# PWR.net
KiCad netlist of a schematic drawn in Altium Designer
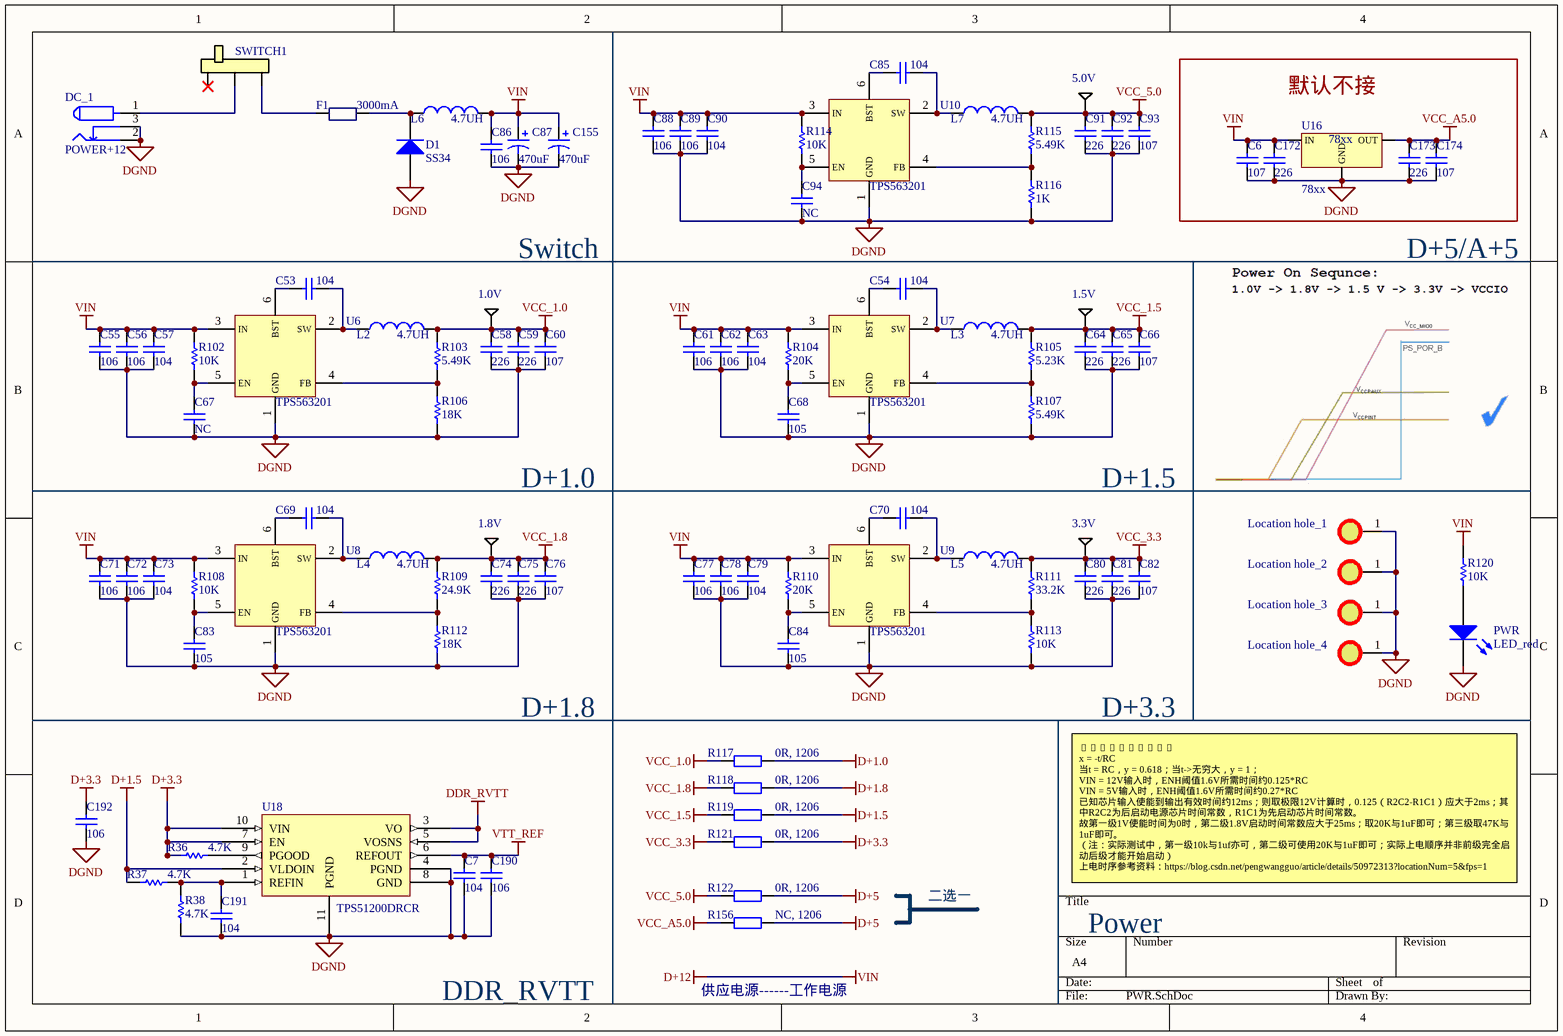
[diagram p0: PWR.SchDoc]

(export (version "E")
  (design (tool "Eeschema 10.0.6"))
  (components
    (comp (ref "1.0V")
      (value "Test")
      (footprint "Test Point")
      (description "Test Point")
      (libsource (lib "ZYNQ7010_add") (part "Test"))
    )
    (comp (ref "1.5V")
      (value "Test")
      (footprint "Test Point")
      (description "Test Point")
      (libsource (lib "ZYNQ7010_add") (part "Test"))
    )
    (comp (ref "1.8V")
      (value "Test")
      (footprint "Test Point")
      (description "Test Point")
      (libsource (lib "ZYNQ7010_add") (part "Test"))
    )
    (comp (ref "3.3V")
      (value "Test")
      (footprint "Test Point")
      (description "Test Point")
      (libsource (lib "ZYNQ7010_add") (part "Test"))
    )
    (comp (ref "5.0V")
      (value "Test")
      (footprint "Test Point")
      (description "Test Point")
      (libsource (lib "ZYNQ7010_add") (part "Test"))
    )
    (comp (ref "C6")
      (value "107")
      (footprint "C 1206_L")
      (description "Capacitor")
      (fields (field (name "PUBLISHER") "Altium Limited"))
      (libsource (lib "Miscellaneous Devices") (part "Cap"))
    )
    (comp (ref "C7")
      (value "104")
      (footprint "C 0402_LL")
      (description "Capacitor")
      (fields (field (name "PUBLISHER") "Altium Limited"))
      (libsource (lib "Miscellaneous Devices") (part "Cap"))
    )
    (comp (ref "C53")
      (value "104")
      (footprint "C 0402_LL")
      (description "Capacitor")
      (fields (field (name "PUBLISHER") "Altium Limited"))
      (libsource (lib "Miscellaneous Devices") (part "Cap"))
    )
    (comp (ref "C54")
      (value "104")
      (footprint "C 0402_LL")
      (description "Capacitor")
      (fields (field (name "PUBLISHER") "Altium Limited"))
      (libsource (lib "Miscellaneous Devices") (part "Cap"))
    )
    (comp (ref "C55")
      (value "106")
      (footprint "C 0805_L")
      (description "Capacitor")
      (fields (field (name "PUBLISHER") "Altium Limited"))
      (libsource (lib "Miscellaneous Devices") (part "Cap"))
    )
    (comp (ref "C56")
      (value "106")
      (footprint "C 0805_L")
      (description "Capacitor")
      (fields (field (name "PUBLISHER") "Altium Limited"))
      (libsource (lib "Miscellaneous Devices") (part "Cap"))
    )
    (comp (ref "C57")
      (value "104")
      (footprint "C 0402_LL")
      (description "Capacitor")
      (fields (field (name "PUBLISHER") "Altium Limited"))
      (libsource (lib "Miscellaneous Devices") (part "Cap"))
    )
    (comp (ref "C58")
      (value "226")
      (footprint "C 0805_L")
      (description "Capacitor")
      (fields (field (name "PUBLISHER") "Altium Limited"))
      (libsource (lib "Miscellaneous Devices") (part "Cap"))
    )
    (comp (ref "C59")
      (value "226")
      (footprint "C 0805_L")
      (description "Capacitor")
      (fields (field (name "PUBLISHER") "Altium Limited"))
      (libsource (lib "Miscellaneous Devices") (part "Cap"))
    )
    (comp (ref "C60")
      (value "107")
      (footprint "C 1206_L")
      (description "Capacitor")
      (fields (field (name "PUBLISHER") "Altium Limited"))
      (libsource (lib "Miscellaneous Devices") (part "Cap"))
    )
    (comp (ref "C61")
      (value "106")
      (footprint "C 0805_L")
      (description "Capacitor")
      (fields (field (name "PUBLISHER") "Altium Limited"))
      (libsource (lib "Miscellaneous Devices") (part "Cap"))
    )
    (comp (ref "C62")
      (value "106")
      (footprint "C 0805_L")
      (description "Capacitor")
      (fields (field (name "PUBLISHER") "Altium Limited"))
      (libsource (lib "Miscellaneous Devices") (part "Cap"))
    )
    (comp (ref "C63")
      (value "104")
      (footprint "C 0402_LL")
      (description "Capacitor")
      (fields (field (name "PUBLISHER") "Altium Limited"))
      (libsource (lib "Miscellaneous Devices") (part "Cap"))
    )
    (comp (ref "C64")
      (value "226")
      (footprint "C 0805_L")
      (description "Capacitor")
      (fields (field (name "PUBLISHER") "Altium Limited"))
      (libsource (lib "Miscellaneous Devices") (part "Cap"))
    )
    (comp (ref "C65")
      (value "226")
      (footprint "C 0805_L")
      (description "Capacitor")
      (fields (field (name "PUBLISHER") "Altium Limited"))
      (libsource (lib "Miscellaneous Devices") (part "Cap"))
    )
    (comp (ref "C66")
      (value "107")
      (footprint "C 1206_L")
      (description "Capacitor")
      (fields (field (name "PUBLISHER") "Altium Limited"))
      (libsource (lib "Miscellaneous Devices") (part "Cap"))
    )
    (comp (ref "C67")
      (value "NC")
      (footprint "C 0402_LL")
      (description "Capacitor")
      (fields (field (name "PUBLISHER") "Altium Limited"))
      (libsource (lib "Miscellaneous Devices") (part "Cap"))
    )
    (comp (ref "C68")
      (value "105")
      (footprint "C 0402_LL")
      (description "Capacitor")
      (fields (field (name "PUBLISHER") "Altium Limited"))
      (libsource (lib "Miscellaneous Devices") (part "Cap"))
    )
    (comp (ref "C69")
      (value "104")
      (footprint "C 0402_LL")
      (description "Capacitor")
      (fields (field (name "PUBLISHER") "Altium Limited"))
      (libsource (lib "Miscellaneous Devices") (part "Cap"))
    )
    (comp (ref "C70")
      (value "104")
      (footprint "C 0402_LL")
      (description "Capacitor")
      (fields (field (name "PUBLISHER") "Altium Limited"))
      (libsource (lib "Miscellaneous Devices") (part "Cap"))
    )
    (comp (ref "C71")
      (value "106")
      (footprint "C 0805_L")
      (description "Capacitor")
      (fields (field (name "PUBLISHER") "Altium Limited"))
      (libsource (lib "Miscellaneous Devices") (part "Cap"))
    )
    (comp (ref "C72")
      (value "106")
      (footprint "C 0805_L")
      (description "Capacitor")
      (fields (field (name "PUBLISHER") "Altium Limited"))
      (libsource (lib "Miscellaneous Devices") (part "Cap"))
    )
    (comp (ref "C73")
      (value "104")
      (footprint "C 0402_LL")
      (description "Capacitor")
      (fields (field (name "PUBLISHER") "Altium Limited"))
      (libsource (lib "Miscellaneous Devices") (part "Cap"))
    )
    (comp (ref "C74")
      (value "226")
      (footprint "C 0805_L")
      (description "Capacitor")
      (fields (field (name "PUBLISHER") "Altium Limited"))
      (libsource (lib "Miscellaneous Devices") (part "Cap"))
    )
    (comp (ref "C75")
      (value "226")
      (footprint "C 0805_L")
      (description "Capacitor")
      (fields (field (name "PUBLISHER") "Altium Limited"))
      (libsource (lib "Miscellaneous Devices") (part "Cap"))
    )
    (comp (ref "C76")
      (value "107")
      (footprint "C 1206_L")
      (description "Capacitor")
      (fields (field (name "PUBLISHER") "Altium Limited"))
      (libsource (lib "Miscellaneous Devices") (part "Cap"))
    )
    (comp (ref "C77")
      (value "106")
      (footprint "C 0805_L")
      (description "Capacitor")
      (fields (field (name "PUBLISHER") "Altium Limited"))
      (libsource (lib "Miscellaneous Devices") (part "Cap"))
    )
    (comp (ref "C78")
      (value "106")
      (footprint "C 0805_L")
      (description "Capacitor")
      (fields (field (name "PUBLISHER") "Altium Limited"))
      (libsource (lib "Miscellaneous Devices") (part "Cap"))
    )
    (comp (ref "C79")
      (value "104")
      (footprint "C 0402_LL")
      (description "Capacitor")
      (fields (field (name "PUBLISHER") "Altium Limited"))
      (libsource (lib "Miscellaneous Devices") (part "Cap"))
    )
    (comp (ref "C80")
      (value "226")
      (footprint "C 0805_L")
      (description "Capacitor")
      (fields (field (name "PUBLISHER") "Altium Limited"))
      (libsource (lib "Miscellaneous Devices") (part "Cap"))
    )
    (comp (ref "C81")
      (value "226")
      (footprint "C 0805_L")
      (description "Capacitor")
      (fields (field (name "PUBLISHER") "Altium Limited"))
      (libsource (lib "Miscellaneous Devices") (part "Cap"))
    )
    (comp (ref "C82")
      (value "107")
      (footprint "C 1206_L")
      (description "Capacitor")
      (fields (field (name "PUBLISHER") "Altium Limited"))
      (libsource (lib "Miscellaneous Devices") (part "Cap"))
    )
    (comp (ref "C83")
      (value "105")
      (footprint "C 0402_LL")
      (description "Capacitor")
      (fields (field (name "PUBLISHER") "Altium Limited"))
      (libsource (lib "Miscellaneous Devices") (part "Cap"))
    )
    (comp (ref "C84")
      (value "105")
      (footprint "C 0402_LL")
      (description "Capacitor")
      (fields (field (name "PUBLISHER") "Altium Limited"))
      (libsource (lib "Miscellaneous Devices") (part "Cap"))
    )
    (comp (ref "C85")
      (value "104")
      (footprint "C 0402_LL")
      (description "Capacitor")
      (fields (field (name "PUBLISHER") "Altium Limited"))
      (libsource (lib "Miscellaneous Devices") (part "Cap"))
    )
    (comp (ref "C86")
      (value "106")
      (footprint "C 0805_L")
      (description "Capacitor")
      (fields (field (name "PUBLISHER") "Altium Limited"))
      (libsource (lib "Miscellaneous Devices") (part "Cap"))
    )
    (comp (ref "C87")
      (value "470uF")
      (footprint "CD D(7343)")
      (description "Polarized Capacitor (Radial)")
      (fields (field (name "Comment") "Cap Pol1") (field (name "PUBLISHER") "Altium Limited"))
      (libsource (lib "Miscellaneous Devices") (part "Cap Pol1"))
    )
    (comp (ref "C88")
      (value "106")
      (footprint "C 0805_L")
      (description "Capacitor")
      (fields (field (name "PUBLISHER") "Altium Limited"))
      (libsource (lib "Miscellaneous Devices") (part "Cap"))
    )
    (comp (ref "C89")
      (value "106")
      (footprint "C 0805_L")
      (description "Capacitor")
      (fields (field (name "PUBLISHER") "Altium Limited"))
      (libsource (lib "Miscellaneous Devices") (part "Cap"))
    )
    (comp (ref "C90")
      (value "104")
      (footprint "C 0402_LL")
      (description "Capacitor")
      (fields (field (name "PUBLISHER") "Altium Limited"))
      (libsource (lib "Miscellaneous Devices") (part "Cap"))
    )
    (comp (ref "C91")
      (value "226")
      (footprint "C 0805_L")
      (description "Capacitor")
      (fields (field (name "PUBLISHER") "Altium Limited"))
      (libsource (lib "Miscellaneous Devices") (part "Cap"))
    )
    (comp (ref "C92")
      (value "226")
      (footprint "C 0805_L")
      (description "Capacitor")
      (fields (field (name "PUBLISHER") "Altium Limited"))
      (libsource (lib "Miscellaneous Devices") (part "Cap"))
    )
    (comp (ref "C93")
      (value "107")
      (footprint "C 1206_L")
      (description "Capacitor")
      (fields (field (name "PUBLISHER") "Altium Limited"))
      (libsource (lib "Miscellaneous Devices") (part "Cap"))
    )
    (comp (ref "C94")
      (value "NC")
      (footprint "C 0402_LL")
      (description "Capacitor")
      (fields (field (name "PUBLISHER") "Altium Limited"))
      (libsource (lib "Miscellaneous Devices") (part "Cap"))
    )
    (comp (ref "C155")
      (value "470uF")
      (footprint "CD D(7343)")
      (description "Polarized Capacitor (Radial)")
      (fields (field (name "Comment") "Cap Pol1") (field (name "PUBLISHER") "Altium Limited"))
      (libsource (lib "Miscellaneous Devices") (part "Cap Pol1"))
    )
    (comp (ref "C172")
      (value "226")
      (footprint "C 0805_L")
      (description "Capacitor")
      (fields (field (name "PUBLISHER") "Altium Limited"))
      (libsource (lib "Miscellaneous Devices") (part "Cap"))
    )
    (comp (ref "C173")
      (value "226")
      (footprint "C 0805_L")
      (description "Capacitor")
      (fields (field (name "PUBLISHER") "Altium Limited"))
      (libsource (lib "Miscellaneous Devices") (part "Cap"))
    )
    (comp (ref "C174")
      (value "107")
      (footprint "C 1206_L")
      (description "Capacitor")
      (fields (field (name "PUBLISHER") "Altium Limited"))
      (libsource (lib "Miscellaneous Devices") (part "Cap"))
    )
    (comp (ref "C190")
      (value "106")
      (footprint "C 0603_L")
      (description "Capacitor")
      (fields (field (name "PUBLISHER") "Altium Limited"))
      (libsource (lib "Miscellaneous Devices") (part "Cap"))
    )
    (comp (ref "C191")
      (value "104")
      (footprint "C 0402_LL")
      (description "Capacitor")
      (fields (field (name "PUBLISHER") "Altium Limited"))
      (libsource (lib "Miscellaneous Devices") (part "Cap"))
    )
    (comp (ref "C192")
      (value "106")
      (footprint "C 0603_L")
      (description "Capacitor")
      (fields (field (name "PUBLISHER") "Altium Limited"))
      (libsource (lib "Miscellaneous Devices") (part "Cap"))
    )
    (comp (ref "D1")
      (value "SS34")
      (footprint "SMA")
      (description "Default Diode")
      (fields (field (name "PUBLISHER") "Altium Limited"))
      (libsource (lib "Miscellaneous Devices") (part "Diode"))
    )
    (comp (ref "DC_1") (value "POWER+12") (footprint "DC-005") (libsource (lib "Sean") (part "POWER")))
    (comp (ref "F1") (value "3000mA") (footprint "FU 1812") (libsource (lib "Sean") (part "PTC")))
    (comp (ref "L2")
      (value "4.7UH")
      (footprint "NR6045")
      (description "Inductor")
      (fields (field (name "PUBLISHER") "Altium Limited"))
      (libsource (lib "Miscellaneous Devices") (part "Inductor"))
    )
    (comp (ref "L3")
      (value "4.7UH")
      (footprint "NR6045")
      (description "Inductor")
      (fields (field (name "PUBLISHER") "Altium Limited"))
      (libsource (lib "Miscellaneous Devices") (part "Inductor"))
    )
    (comp (ref "L4")
      (value "4.7UH")
      (footprint "NR6045")
      (description "Inductor")
      (fields (field (name "PUBLISHER") "Altium Limited"))
      (libsource (lib "Miscellaneous Devices") (part "Inductor"))
    )
    (comp (ref "L5")
      (value "4.7UH")
      (footprint "NR6045")
      (description "Inductor")
      (fields (field (name "PUBLISHER") "Altium Limited"))
      (libsource (lib "Miscellaneous Devices") (part "Inductor"))
    )
    (comp (ref "L6")
      (value "4.7UH")
      (footprint "NR6045")
      (description "Inductor")
      (fields (field (name "PUBLISHER") "Altium Limited"))
      (libsource (lib "Miscellaneous Devices") (part "Inductor"))
    )
    (comp (ref "L7")
      (value "4.7UH")
      (footprint "NR6045")
      (description "Inductor")
      (fields (field (name "PUBLISHER") "Altium Limited"))
      (libsource (lib "Miscellaneous Devices") (part "Inductor"))
    )
    (comp (ref "Location hole_1")
      (value "Touch")
      (footprint "M3x4+6_N")
      (libsource (lib "Sean") (part "Touch"))
    )
    (comp (ref "Location hole_2")
      (value "Touch")
      (footprint "M3x4+6_N")
      (libsource (lib "Sean") (part "Touch"))
    )
    (comp (ref "Location hole_3")
      (value "Touch")
      (footprint "M3x4+6_N")
      (libsource (lib "Sean") (part "Touch"))
    )
    (comp (ref "Location hole_4")
      (value "Touch")
      (footprint "M3x4+6_N")
      (libsource (lib "Sean") (part "Touch"))
    )
    (comp (ref "PWR")
      (value "LED_red")
      (footprint "LED 0603W")
      (description "Typical INFRARED GaAs LED")
      (fields (field (name "PUBLISHER") "Altium Limited"))
      (libsource (lib "Miscellaneous Devices") (part "LED0"))
    )
    (comp (ref "R36")
      (value "4.7K")
      (footprint "R 0402_L")
      (description "Resistor")
      (fields (field (name "PUBLISHER") "Altium Limited"))
      (libsource (lib "Miscellaneous Devices") (part "Res1"))
    )
    (comp (ref "R37")
      (value "4.7K")
      (footprint "R 0402_L")
      (description "Resistor")
      (fields (field (name "PUBLISHER") "Altium Limited"))
      (libsource (lib "Miscellaneous Devices") (part "Res1"))
    )
    (comp (ref "R38")
      (value "4.7K")
      (footprint "R 0402_L")
      (description "Resistor")
      (fields (field (name "PUBLISHER") "Altium Limited"))
      (libsource (lib "Miscellaneous Devices") (part "Res1"))
    )
    (comp (ref "R102")
      (value "10K")
      (footprint "R 0603_L")
      (description "Resistor")
      (fields (field (name "PUBLISHER") "Altium Limited"))
      (libsource (lib "Miscellaneous Devices") (part "Res1"))
    )
    (comp (ref "R103")
      (value "5.49K")
      (footprint "R 0603_L")
      (description "Resistor")
      (fields (field (name "PUBLISHER") "Altium Limited"))
      (libsource (lib "Miscellaneous Devices") (part "Res1"))
    )
    (comp (ref "R104")
      (value "20K")
      (footprint "R 0603_L")
      (description "Resistor")
      (fields (field (name "PUBLISHER") "Altium Limited"))
      (libsource (lib "Miscellaneous Devices") (part "Res1"))
    )
    (comp (ref "R105")
      (value "5.23K")
      (footprint "R 0603_L")
      (description "Resistor")
      (fields (field (name "PUBLISHER") "Altium Limited"))
      (libsource (lib "Miscellaneous Devices") (part "Res1"))
    )
    (comp (ref "R106")
      (value "18K")
      (footprint "R 0603_L")
      (description "Resistor")
      (fields (field (name "PUBLISHER") "Altium Limited"))
      (libsource (lib "Miscellaneous Devices") (part "Res1"))
    )
    (comp (ref "R107")
      (value "5.49K")
      (footprint "R 0603_L")
      (description "Resistor")
      (fields (field (name "PUBLISHER") "Altium Limited"))
      (libsource (lib "Miscellaneous Devices") (part "Res1"))
    )
    (comp (ref "R108")
      (value "10K")
      (footprint "R 0603_L")
      (description "Resistor")
      (fields (field (name "PUBLISHER") "Altium Limited"))
      (libsource (lib "Miscellaneous Devices") (part "Res1"))
    )
    (comp (ref "R109")
      (value "24.9K")
      (footprint "R 0603_L")
      (description "Resistor")
      (fields (field (name "PUBLISHER") "Altium Limited"))
      (libsource (lib "Miscellaneous Devices") (part "Res1"))
    )
    (comp (ref "R110")
      (value "20K")
      (footprint "R 0603_L")
      (description "Resistor")
      (fields (field (name "PUBLISHER") "Altium Limited"))
      (libsource (lib "Miscellaneous Devices") (part "Res1"))
    )
    (comp (ref "R111")
      (value "33.2K")
      (footprint "R 0603_L")
      (description "Resistor")
      (fields (field (name "PUBLISHER") "Altium Limited"))
      (libsource (lib "Miscellaneous Devices") (part "Res1"))
    )
    (comp (ref "R112")
      (value "18K")
      (footprint "R 0603_L")
      (description "Resistor")
      (fields (field (name "PUBLISHER") "Altium Limited"))
      (libsource (lib "Miscellaneous Devices") (part "Res1"))
    )
    (comp (ref "R113")
      (value "10K")
      (footprint "R 0603_L")
      (description "Resistor")
      (fields (field (name "PUBLISHER") "Altium Limited"))
      (libsource (lib "Miscellaneous Devices") (part "Res1"))
    )
    (comp (ref "R114")
      (value "10K")
      (footprint "R 0603_L")
      (description "Resistor")
      (fields (field (name "PUBLISHER") "Altium Limited"))
      (libsource (lib "Miscellaneous Devices") (part "Res1"))
    )
    (comp (ref "R115")
      (value "5.49K")
      (footprint "R 0603_L")
      (description "Resistor")
      (fields (field (name "PUBLISHER") "Altium Limited"))
      (libsource (lib "Miscellaneous Devices") (part "Res1"))
    )
    (comp (ref "R116")
      (value "1K")
      (footprint "R 0603_L")
      (description "Resistor")
      (fields (field (name "PUBLISHER") "Altium Limited"))
      (libsource (lib "Miscellaneous Devices") (part "Res1"))
    )
    (comp (ref "R117")
      (value "0R, 1206")
      (footprint "R 1206_L")
      (description "Resistor")
      (fields (field (name "PUBLISHER") "Altium Limited"))
      (libsource (lib "Miscellaneous Devices") (part "Res2"))
    )
    (comp (ref "R118")
      (value "0R, 1206")
      (footprint "R 1206_L")
      (description "Resistor")
      (fields (field (name "PUBLISHER") "Altium Limited"))
      (libsource (lib "Miscellaneous Devices") (part "Res2"))
    )
    (comp (ref "R119")
      (value "0R, 1206")
      (footprint "R 1206_L")
      (description "Resistor")
      (fields (field (name "PUBLISHER") "Altium Limited"))
      (libsource (lib "Miscellaneous Devices") (part "Res2"))
    )
    (comp (ref "R120")
      (value "10K")
      (footprint "R 0603_L")
      (description "Resistor")
      (fields (field (name "PUBLISHER") "Altium Limited"))
      (libsource (lib "Miscellaneous Devices") (part "Res1"))
    )
    (comp (ref "R121")
      (value "0R, 1206")
      (footprint "R 1206_L")
      (description "Resistor")
      (fields (field (name "PUBLISHER") "Altium Limited"))
      (libsource (lib "Miscellaneous Devices") (part "Res2"))
    )
    (comp (ref "R122")
      (value "0R, 1206")
      (footprint "R 1206_L")
      (description "Resistor")
      (fields (field (name "PUBLISHER") "Altium Limited"))
      (libsource (lib "Miscellaneous Devices") (part "Res2"))
    )
    (comp (ref "R156")
      (value "NC, 1206")
      (footprint "R 1206_L")
      (description "Resistor")
      (fields (field (name "PUBLISHER") "Altium Limited"))
      (libsource (lib "Miscellaneous Devices") (part "Res2"))
    )
    (comp (ref "SWITCH1")
      (value "Switch")
      (footprint "SS-12D10")
      (libsource (lib "XCZU15_add") (part "Switch"))
    )
    (comp (ref "U6")
      (value "TPS563201")
      (footprint "SOT23-6N")
      (description "TPS563201, BUCK, 3A")
      (libsource (lib "ZYNQ7010_add") (part "TPS563201"))
    )
    (comp (ref "U7")
      (value "TPS563201")
      (footprint "SOT23-6N")
      (description "TPS563201, BUCK, 3A")
      (libsource (lib "ZYNQ7010_add") (part "TPS563201"))
    )
    (comp (ref "U8")
      (value "TPS563201")
      (footprint "SOT23-6N")
      (description "TPS563201, BUCK, 3A")
      (libsource (lib "ZYNQ7010_add") (part "TPS563201"))
    )
    (comp (ref "U9")
      (value "TPS563201")
      (footprint "SOT23-6N")
      (description "TPS563201, BUCK, 3A")
      (libsource (lib "ZYNQ7010_add") (part "TPS563201"))
    )
    (comp (ref "U10")
      (value "TPS563201")
      (footprint "SOT23-6N")
      (description "TPS563201, BUCK, 3A")
      (libsource (lib "ZYNQ7010_add") (part "TPS563201"))
    )
    (comp (ref "U16") (value "78xx") (footprint "TO252") (libsource (lib "Schlib1") (part "78xx")))
    (comp (ref "U18")
      (value "TPS51200DRCR")
      (footprint "VSON")
      (description "DDR 终端稳压器")
      (fields (field (name "MANUFACTURER") "TI"))
      (libsource (lib "ZYNQ7010_add") (part "TPS51200"))
    )
  )
  (nets
    (net (code "1") (name "D+1.0") (class "Default")
      (node (ref "R117") (pin "2") (pinfunction "2_2") (pintype "passive"))
    )
    (net (code "2") (name "D+1.5") (class "Default")
      (node (ref "R119") (pin "2") (pinfunction "2_2") (pintype "passive"))
      (node (ref "R37") (pin "1") (pinfunction "1_1") (pintype "passive"))
      (node (ref "U18") (pin "2") (pinfunction "VLDOIN_2") (pintype "input"))
    )
    (net (code "3") (name "D+1.8") (class "Default")
      (node (ref "R118") (pin "2") (pinfunction "2_2") (pintype "passive"))
    )
    (net (code "4") (name "D+3.3") (class "Default")
      (node (ref "C192") (pin "2") (pinfunction "2_2") (pintype "passive"))
      (node (ref "R121") (pin "2") (pinfunction "2_2") (pintype "passive"))
      (node (ref "R36") (pin "1") (pinfunction "1_1") (pintype "passive"))
      (node (ref "U18") (pin "10") (pinfunction "VIN_10") (pintype "input"))
      (node (ref "U18") (pin "7") (pinfunction "EN_7") (pintype "input"))
    )
    (net (code "5") (name "D+5") (class "Default")
      (node (ref "R122") (pin "2") (pinfunction "2_2") (pintype "passive"))
      (node (ref "R156") (pin "2") (pinfunction "2_2") (pintype "passive"))
    )
    (net (code "6") (name "D+12") (class "Default")
      (node (ref "C155") (pin "1") (pinfunction "1_1") (pintype "passive"))
      (node (ref "C172") (pin "1") (pinfunction "1_1") (pintype "passive"))
      (node (ref "C55") (pin "1") (pinfunction "1_1") (pintype "passive"))
      (node (ref "C56") (pin "1") (pinfunction "1_1") (pintype "passive"))
      (node (ref "C57") (pin "1") (pinfunction "1_1") (pintype "passive"))
      (node (ref "C6") (pin "1") (pinfunction "1_1") (pintype "passive"))
      (node (ref "C61") (pin "1") (pinfunction "1_1") (pintype "passive"))
      (node (ref "C62") (pin "1") (pinfunction "1_1") (pintype "passive"))
      (node (ref "C63") (pin "1") (pinfunction "1_1") (pintype "passive"))
      (node (ref "C71") (pin "1") (pinfunction "1_1") (pintype "passive"))
      (node (ref "C72") (pin "1") (pinfunction "1_1") (pintype "passive"))
      (node (ref "C73") (pin "1") (pinfunction "1_1") (pintype "passive"))
      (node (ref "C77") (pin "1") (pinfunction "1_1") (pintype "passive"))
      (node (ref "C78") (pin "1") (pinfunction "1_1") (pintype "passive"))
      (node (ref "C79") (pin "1") (pinfunction "1_1") (pintype "passive"))
      (node (ref "C86") (pin "1") (pinfunction "1_1") (pintype "passive"))
      (node (ref "C87") (pin "1") (pinfunction "1_1") (pintype "passive"))
      (node (ref "C88") (pin "1") (pinfunction "1_1") (pintype "passive"))
      (node (ref "C89") (pin "1") (pinfunction "1_1") (pintype "passive"))
      (node (ref "C90") (pin "1") (pinfunction "1_1") (pintype "passive"))
      (node (ref "L6") (pin "2") (pinfunction "2_2") (pintype "passive"))
      (node (ref "R102") (pin "2") (pinfunction "2_2") (pintype "passive"))
      (node (ref "R104") (pin "2") (pinfunction "2_2") (pintype "passive"))
      (node (ref "R108") (pin "2") (pinfunction "2_2") (pintype "passive"))
      (node (ref "R110") (pin "2") (pinfunction "2_2") (pintype "passive"))
      (node (ref "R114") (pin "1") (pinfunction "1_1") (pintype "passive"))
      (node (ref "R120") (pin "2") (pinfunction "2_2") (pintype "passive"))
      (node (ref "U10") (pin "3") (pinfunction "IN_3") (pintype "passive"))
      (node (ref "U16") (pin "1") (pinfunction "IN_1") (pintype "passive"))
      (node (ref "U6") (pin "3") (pinfunction "IN_3") (pintype "passive"))
      (node (ref "U7") (pin "3") (pinfunction "IN_3") (pintype "passive"))
      (node (ref "U8") (pin "3") (pinfunction "IN_3") (pintype "passive"))
      (node (ref "U9") (pin "3") (pinfunction "IN_3") (pintype "passive"))
    )
    (net (code "7") (name "DDR_RVTT") (class "Default")
      (node (ref "U18") (pin "3") (pinfunction "VO_3") (pintype "output"))
      (node (ref "U18") (pin "5") (pinfunction "VOSNS_5") (pintype "input"))
    )
    (net (code "8") (name "DGND") (class "Default")
      (node (ref "C155") (pin "2") (pinfunction "2_2") (pintype "passive"))
      (node (ref "C172") (pin "2") (pinfunction "2_2") (pintype "passive"))
      (node (ref "C173") (pin "2") (pinfunction "2_2") (pintype "passive"))
      (node (ref "C174") (pin "2") (pinfunction "2_2") (pintype "passive"))
      (node (ref "C190") (pin "1") (pinfunction "1_1") (pintype "passive"))
      (node (ref "C191") (pin "1") (pinfunction "1_1") (pintype "passive"))
      (node (ref "C192") (pin "1") (pinfunction "1_1") (pintype "passive"))
      (node (ref "C55") (pin "2") (pinfunction "2_2") (pintype "passive"))
      (node (ref "C56") (pin "2") (pinfunction "2_2") (pintype "passive"))
      (node (ref "C57") (pin "2") (pinfunction "2_2") (pintype "passive"))
      (node (ref "C58") (pin "2") (pinfunction "2_2") (pintype "passive"))
      (node (ref "C59") (pin "2") (pinfunction "2_2") (pintype "passive"))
      (node (ref "C6") (pin "2") (pinfunction "2_2") (pintype "passive"))
      (node (ref "C60") (pin "2") (pinfunction "2_2") (pintype "passive"))
      (node (ref "C61") (pin "2") (pinfunction "2_2") (pintype "passive"))
      (node (ref "C62") (pin "2") (pinfunction "2_2") (pintype "passive"))
      (node (ref "C63") (pin "2") (pinfunction "2_2") (pintype "passive"))
      (node (ref "C64") (pin "2") (pinfunction "2_2") (pintype "passive"))
      (node (ref "C65") (pin "2") (pinfunction "2_2") (pintype "passive"))
      (node (ref "C66") (pin "2") (pinfunction "2_2") (pintype "passive"))
      (node (ref "C67") (pin "2") (pinfunction "2_2") (pintype "passive"))
      (node (ref "C68") (pin "2") (pinfunction "2_2") (pintype "passive"))
      (node (ref "C7") (pin "1") (pinfunction "1_1") (pintype "passive"))
      (node (ref "C71") (pin "2") (pinfunction "2_2") (pintype "passive"))
      (node (ref "C72") (pin "2") (pinfunction "2_2") (pintype "passive"))
      (node (ref "C73") (pin "2") (pinfunction "2_2") (pintype "passive"))
      (node (ref "C74") (pin "2") (pinfunction "2_2") (pintype "passive"))
      (node (ref "C75") (pin "2") (pinfunction "2_2") (pintype "passive"))
      (node (ref "C76") (pin "2") (pinfunction "2_2") (pintype "passive"))
      (node (ref "C77") (pin "2") (pinfunction "2_2") (pintype "passive"))
      (node (ref "C78") (pin "2") (pinfunction "2_2") (pintype "passive"))
      (node (ref "C79") (pin "2") (pinfunction "2_2") (pintype "passive"))
      (node (ref "C80") (pin "2") (pinfunction "2_2") (pintype "passive"))
      (node (ref "C81") (pin "2") (pinfunction "2_2") (pintype "passive"))
      (node (ref "C82") (pin "2") (pinfunction "2_2") (pintype "passive"))
      (node (ref "C83") (pin "2") (pinfunction "2_2") (pintype "passive"))
      (node (ref "C84") (pin "2") (pinfunction "2_2") (pintype "passive"))
      (node (ref "C86") (pin "2") (pinfunction "2_2") (pintype "passive"))
      (node (ref "C87") (pin "2") (pinfunction "2_2") (pintype "passive"))
      (node (ref "C88") (pin "2") (pinfunction "2_2") (pintype "passive"))
      (node (ref "C89") (pin "2") (pinfunction "2_2") (pintype "passive"))
      (node (ref "C90") (pin "2") (pinfunction "2_2") (pintype "passive"))
      (node (ref "C91") (pin "2") (pinfunction "2_2") (pintype "passive"))
      (node (ref "C92") (pin "2") (pinfunction "2_2") (pintype "passive"))
      (node (ref "C93") (pin "2") (pinfunction "2_2") (pintype "passive"))
      (node (ref "C94") (pin "2") (pinfunction "2_2") (pintype "passive"))
      (node (ref "D1") (pin "1") (pinfunction "A_1") (pintype "passive"))
      (node (ref "DC_1") (pin "2") (pintype "passive"))
      (node (ref "DC_1") (pin "3") (pintype "passive"))
      (node (ref "Location hole_1") (pin "1") (pinfunction "1_1") (pintype "passive"))
      (node (ref "Location hole_2") (pin "1") (pinfunction "1_1") (pintype "passive"))
      (node (ref "Location hole_3") (pin "1") (pinfunction "1_1") (pintype "passive"))
      (node (ref "Location hole_4") (pin "1") (pinfunction "1_1") (pintype "passive"))
      (node (ref "PWR") (pin "2") (pinfunction "K_2") (pintype "passive"))
      (node (ref "R106") (pin "1") (pinfunction "1_1") (pintype "passive"))
      (node (ref "R107") (pin "1") (pinfunction "1_1") (pintype "passive"))
      (node (ref "R112") (pin "1") (pinfunction "1_1") (pintype "passive"))
      (node (ref "R113") (pin "1") (pinfunction "1_1") (pintype "passive"))
      (node (ref "R116") (pin "1") (pinfunction "1_1") (pintype "passive"))
      (node (ref "R38") (pin "1") (pinfunction "1_1") (pintype "passive"))
      (node (ref "U10") (pin "1") (pinfunction "GND_1") (pintype "passive"))
      (node (ref "U16") (pin "2") (pinfunction "GND_2") (pintype "passive"))
      (node (ref "U18") (pin "11") (pinfunction "PGND_11") (pintype "power_in"))
      (node (ref "U18") (pin "4") (pinfunction "PGND_4") (pintype "power_in"))
      (node (ref "U18") (pin "8") (pinfunction "GND_8") (pintype "power_in"))
      (node (ref "U6") (pin "1") (pinfunction "GND_1") (pintype "passive"))
      (node (ref "U7") (pin "1") (pinfunction "GND_1") (pintype "passive"))
      (node (ref "U8") (pin "1") (pinfunction "GND_1") (pintype "passive"))
      (node (ref "U9") (pin "1") (pinfunction "GND_1") (pintype "passive"))
    )
    (net (code "9") (name "Net-(D1-K)") (class "Default")
      (node (ref "D1") (pin "2") (pinfunction "K_2") (pintype "passive"))
      (node (ref "F1") (pin "1") (pinfunction "1_1") (pintype "passive"))
      (node (ref "L6") (pin "1") (pinfunction "1_1") (pintype "passive"))
    )
    (net (code "10") (name "Net-(DC_1-Pad1)") (class "Default")
      (node (ref "DC_1") (pin "1") (pintype "passive"))
      (node (ref "SWITCH1") (pin "2") (pinfunction "2_2") (pintype "passive"))
    )
    (net (code "11") (name "Net-(F1-Pad2)") (class "Default")
      (node (ref "F1") (pin "2") (pinfunction "2_2") (pintype "passive"))
      (node (ref "SWITCH1") (pin "3") (pinfunction "3_3") (pintype "passive"))
    )
    (net (code "12") (name "Net-(PWR-A)") (class "Default")
      (node (ref "PWR") (pin "1") (pinfunction "A_1") (pintype "passive"))
      (node (ref "R120") (pin "1") (pinfunction "1_1") (pintype "passive"))
    )
    (net (code "13") (name "Net-(U6-BST)") (class "Default")
      (node (ref "C53") (pin "2") (pinfunction "2_2") (pintype "passive"))
      (node (ref "U6") (pin "6") (pinfunction "BST_6") (pintype "passive"))
    )
    (net (code "14") (name "Net-(U6-EN)") (class "Default")
      (node (ref "C67") (pin "1") (pinfunction "1_1") (pintype "passive"))
      (node (ref "R102") (pin "1") (pinfunction "1_1") (pintype "passive"))
      (node (ref "U6") (pin "5") (pinfunction "EN_5") (pintype "passive"))
    )
    (net (code "15") (name "Net-(U6-FB)") (class "Default")
      (node (ref "R103") (pin "1") (pinfunction "1_1") (pintype "passive"))
      (node (ref "R106") (pin "2") (pinfunction "2_2") (pintype "passive"))
      (node (ref "U6") (pin "4") (pinfunction "FB_4") (pintype "passive"))
    )
    (net (code "16") (name "Net-(U6-SW)") (class "Default")
      (node (ref "C53") (pin "1") (pinfunction "1_1") (pintype "passive"))
      (node (ref "L2") (pin "1") (pinfunction "1_1") (pintype "passive"))
      (node (ref "U6") (pin "2") (pinfunction "SW_2") (pintype "passive"))
    )
    (net (code "17") (name "Net-(U7-BST)") (class "Default")
      (node (ref "C54") (pin "2") (pinfunction "2_2") (pintype "passive"))
      (node (ref "U7") (pin "6") (pinfunction "BST_6") (pintype "passive"))
    )
    (net (code "18") (name "Net-(U7-EN)") (class "Default")
      (node (ref "C68") (pin "1") (pinfunction "1_1") (pintype "passive"))
      (node (ref "R104") (pin "1") (pinfunction "1_1") (pintype "passive"))
      (node (ref "U7") (pin "5") (pinfunction "EN_5") (pintype "passive"))
    )
    (net (code "19") (name "Net-(U7-FB)") (class "Default")
      (node (ref "R105") (pin "1") (pinfunction "1_1") (pintype "passive"))
      (node (ref "R107") (pin "2") (pinfunction "2_2") (pintype "passive"))
      (node (ref "U7") (pin "4") (pinfunction "FB_4") (pintype "passive"))
    )
    (net (code "20") (name "Net-(U7-SW)") (class "Default")
      (node (ref "C54") (pin "1") (pinfunction "1_1") (pintype "passive"))
      (node (ref "L3") (pin "1") (pinfunction "1_1") (pintype "passive"))
      (node (ref "U7") (pin "2") (pinfunction "SW_2") (pintype "passive"))
    )
    (net (code "21") (name "Net-(U8-BST)") (class "Default")
      (node (ref "C69") (pin "2") (pinfunction "2_2") (pintype "passive"))
      (node (ref "U8") (pin "6") (pinfunction "BST_6") (pintype "passive"))
    )
    (net (code "22") (name "Net-(U8-EN)") (class "Default")
      (node (ref "C83") (pin "1") (pinfunction "1_1") (pintype "passive"))
      (node (ref "R108") (pin "1") (pinfunction "1_1") (pintype "passive"))
      (node (ref "U8") (pin "5") (pinfunction "EN_5") (pintype "passive"))
    )
    (net (code "23") (name "Net-(U8-FB)") (class "Default")
      (node (ref "R109") (pin "1") (pinfunction "1_1") (pintype "passive"))
      (node (ref "R112") (pin "2") (pinfunction "2_2") (pintype "passive"))
      (node (ref "U8") (pin "4") (pinfunction "FB_4") (pintype "passive"))
    )
    (net (code "24") (name "Net-(U8-SW)") (class "Default")
      (node (ref "C69") (pin "1") (pinfunction "1_1") (pintype "passive"))
      (node (ref "L4") (pin "1") (pinfunction "1_1") (pintype "passive"))
      (node (ref "U8") (pin "2") (pinfunction "SW_2") (pintype "passive"))
    )
    (net (code "25") (name "Net-(U9-BST)") (class "Default")
      (node (ref "C70") (pin "2") (pinfunction "2_2") (pintype "passive"))
      (node (ref "U9") (pin "6") (pinfunction "BST_6") (pintype "passive"))
    )
    (net (code "26") (name "Net-(U9-EN)") (class "Default")
      (node (ref "C84") (pin "1") (pinfunction "1_1") (pintype "passive"))
      (node (ref "R110") (pin "1") (pinfunction "1_1") (pintype "passive"))
      (node (ref "U9") (pin "5") (pinfunction "EN_5") (pintype "passive"))
    )
    (net (code "27") (name "Net-(U9-FB)") (class "Default")
      (node (ref "R111") (pin "1") (pinfunction "1_1") (pintype "passive"))
      (node (ref "R113") (pin "2") (pinfunction "2_2") (pintype "passive"))
      (node (ref "U9") (pin "4") (pinfunction "FB_4") (pintype "passive"))
    )
    (net (code "28") (name "Net-(U9-SW)") (class "Default")
      (node (ref "C70") (pin "1") (pinfunction "1_1") (pintype "passive"))
      (node (ref "L5") (pin "1") (pinfunction "1_1") (pintype "passive"))
      (node (ref "U9") (pin "2") (pinfunction "SW_2") (pintype "passive"))
    )
    (net (code "29") (name "Net-(U10-BST)") (class "Default")
      (node (ref "C85") (pin "2") (pinfunction "2_2") (pintype "passive"))
      (node (ref "U10") (pin "6") (pinfunction "BST_6") (pintype "passive"))
    )
    (net (code "30") (name "Net-(U10-EN)") (class "Default")
      (node (ref "C94") (pin "1") (pinfunction "1_1") (pintype "passive"))
      (node (ref "R114") (pin "2") (pinfunction "2_2") (pintype "passive"))
      (node (ref "U10") (pin "5") (pinfunction "EN_5") (pintype "passive"))
    )
    (net (code "31") (name "Net-(U10-FB)") (class "Default")
      (node (ref "R115") (pin "1") (pinfunction "1_1") (pintype "passive"))
      (node (ref "R116") (pin "2") (pinfunction "2_2") (pintype "passive"))
      (node (ref "U10") (pin "4") (pinfunction "FB_4") (pintype "passive"))
    )
    (net (code "32") (name "Net-(U10-SW)") (class "Default")
      (node (ref "C85") (pin "1") (pinfunction "1_1") (pintype "passive"))
      (node (ref "L7") (pin "1") (pinfunction "1_1") (pintype "passive"))
      (node (ref "U10") (pin "2") (pinfunction "SW_2") (pintype "passive"))
    )
    (net (code "33") (name "Net-(U18-PGOOD)") (class "Default")
      (node (ref "R36") (pin "2") (pinfunction "2_2") (pintype "passive"))
      (node (ref "U18") (pin "9") (pinfunction "PGOOD_9") (pintype "output"))
    )
    (net (code "34") (name "Net-(U18-REFIN)") (class "Default")
      (node (ref "C191") (pin "2") (pinfunction "2_2") (pintype "passive"))
      (node (ref "R37") (pin "2") (pinfunction "2_2") (pintype "passive"))
      (node (ref "R38") (pin "2") (pinfunction "2_2") (pintype "passive"))
      (node (ref "U18") (pin "1") (pinfunction "REFIN_1") (pintype "input"))
    )
    (net (code "35") (name "VCC_1.0") (class "Default")
      (node (ref "1.0V") (pin "1") (pinfunction "Test_1") (pintype "passive"))
      (node (ref "C58") (pin "1") (pinfunction "1_1") (pintype "passive"))
      (node (ref "C59") (pin "1") (pinfunction "1_1") (pintype "passive"))
      (node (ref "C60") (pin "1") (pinfunction "1_1") (pintype "passive"))
      (node (ref "L2") (pin "2") (pinfunction "2_2") (pintype "passive"))
      (node (ref "R103") (pin "2") (pinfunction "2_2") (pintype "passive"))
      (node (ref "R117") (pin "1") (pinfunction "1_1") (pintype "passive"))
    )
    (net (code "36") (name "VCC_1.5") (class "Default")
      (node (ref "1.5V") (pin "1") (pinfunction "Test_1") (pintype "passive"))
      (node (ref "C64") (pin "1") (pinfunction "1_1") (pintype "passive"))
      (node (ref "C65") (pin "1") (pinfunction "1_1") (pintype "passive"))
      (node (ref "C66") (pin "1") (pinfunction "1_1") (pintype "passive"))
      (node (ref "L3") (pin "2") (pinfunction "2_2") (pintype "passive"))
      (node (ref "R105") (pin "2") (pinfunction "2_2") (pintype "passive"))
      (node (ref "R119") (pin "1") (pinfunction "1_1") (pintype "passive"))
    )
    (net (code "37") (name "VCC_1.8") (class "Default")
      (node (ref "1.8V") (pin "1") (pinfunction "Test_1") (pintype "passive"))
      (node (ref "C74") (pin "1") (pinfunction "1_1") (pintype "passive"))
      (node (ref "C75") (pin "1") (pinfunction "1_1") (pintype "passive"))
      (node (ref "C76") (pin "1") (pinfunction "1_1") (pintype "passive"))
      (node (ref "L4") (pin "2") (pinfunction "2_2") (pintype "passive"))
      (node (ref "R109") (pin "2") (pinfunction "2_2") (pintype "passive"))
      (node (ref "R118") (pin "1") (pinfunction "1_1") (pintype "passive"))
    )
    (net (code "38") (name "VCC_3.3") (class "Default")
      (node (ref "3.3V") (pin "1") (pinfunction "Test_1") (pintype "passive"))
      (node (ref "C80") (pin "1") (pinfunction "1_1") (pintype "passive"))
      (node (ref "C81") (pin "1") (pinfunction "1_1") (pintype "passive"))
      (node (ref "C82") (pin "1") (pinfunction "1_1") (pintype "passive"))
      (node (ref "L5") (pin "2") (pinfunction "2_2") (pintype "passive"))
      (node (ref "R111") (pin "2") (pinfunction "2_2") (pintype "passive"))
      (node (ref "R121") (pin "1") (pinfunction "1_1") (pintype "passive"))
    )
    (net (code "39") (name "VCC_5.0") (class "Default")
      (node (ref "5.0V") (pin "1") (pinfunction "Test_1") (pintype "passive"))
      (node (ref "C91") (pin "1") (pinfunction "1_1") (pintype "passive"))
      (node (ref "C92") (pin "1") (pinfunction "1_1") (pintype "passive"))
      (node (ref "C93") (pin "1") (pinfunction "1_1") (pintype "passive"))
      (node (ref "L7") (pin "2") (pinfunction "2_2") (pintype "passive"))
      (node (ref "R115") (pin "2") (pinfunction "2_2") (pintype "passive"))
      (node (ref "R122") (pin "1") (pinfunction "1_1") (pintype "passive"))
    )
    (net (code "40") (name "VCC_A5.0") (class "Default")
      (node (ref "C173") (pin "1") (pinfunction "1_1") (pintype "passive"))
      (node (ref "C174") (pin "1") (pinfunction "1_1") (pintype "passive"))
      (node (ref "R156") (pin "1") (pinfunction "1_1") (pintype "passive"))
      (node (ref "U16") (pin "3") (pinfunction "OUT_3") (pintype "passive"))
    )
    (net (code "41") (name "VTT_REF") (class "Default")
      (node (ref "C190") (pin "2") (pinfunction "2_2") (pintype "passive"))
      (node (ref "C7") (pin "2") (pinfunction "2_2") (pintype "passive"))
      (node (ref "U18") (pin "6") (pinfunction "REFOUT_6") (pintype "output"))
    )
    (net (code "42") (name "unconnected-(SWITCH1-Pad1)") (class "Default")
      (node (ref "SWITCH1") (pin "1") (pinfunction "1_1") (pintype "passive+no_connect"))
    )
  )
)
